# Sheet1.net
KiCad netlist of a schematic drawn in Altium Designer
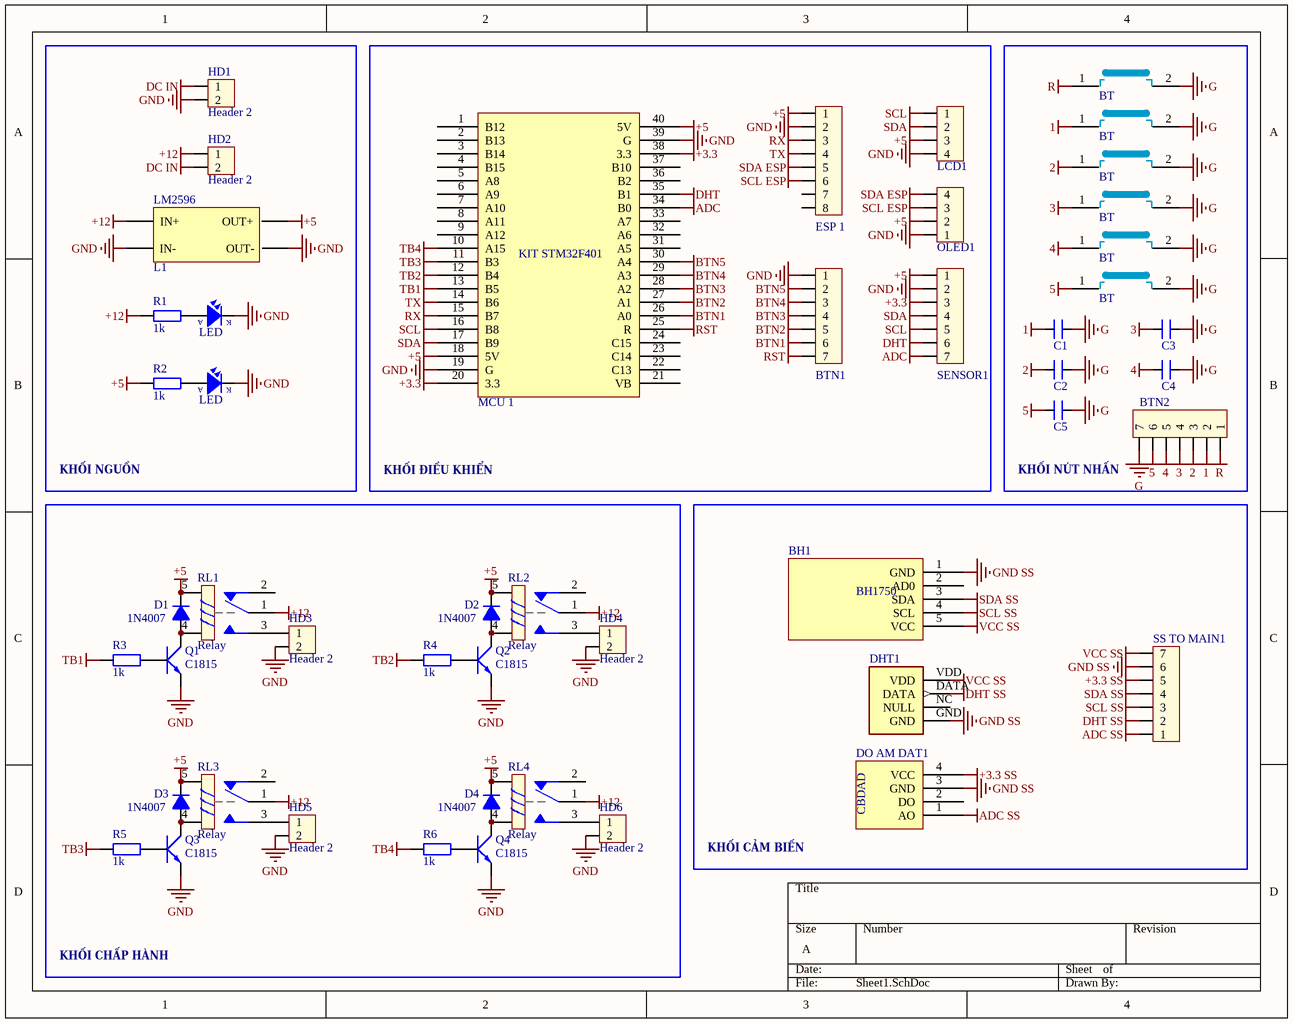
[diagram p0: Sheet1.SchDoc]

(export (version "E")
  (design (tool "Eeschema 10.0.6"))
  (components
    (comp (ref "BH1") (value "BH1750") (footprint "BH1750") (libsource (lib "MY_LIBRARY") (part "BH1750")))
    (comp (ref "BT1") (value "BT") (footprint "SW4") (libsource (lib "MY_LIBRARY") (part "BUTTON")))
    (comp (ref "BT2") (value "BT") (footprint "SW4") (libsource (lib "MY_LIBRARY") (part "BUTTON")))
    (comp (ref "BT3") (value "BT") (footprint "SW4") (libsource (lib "MY_LIBRARY") (part "BUTTON")))
    (comp (ref "BT4") (value "BT") (footprint "SW4") (libsource (lib "MY_LIBRARY") (part "BUTTON")))
    (comp (ref "BT5") (value "BT") (footprint "SW4") (libsource (lib "MY_LIBRARY") (part "BUTTON")))
    (comp (ref "BT6") (value "BT") (footprint "SW4") (libsource (lib "MY_LIBRARY") (part "BUTTON")))
    (comp (ref "BTN1")
      (value "JP7")
      (footprint "CON7")
      (description "Connector 7")
      (libsource (lib "MY_LIBRARY") (part "Con7"))
    )
    (comp (ref "BTN2")
      (value "JP7")
      (footprint "CON7")
      (description "Connector 7")
      (libsource (lib "MY_LIBRARY") (part "Con7"))
    )
    (comp (ref "C1") (value "CAP gom") (footprint "CN1") (libsource (lib "MY_LIBRARY") (part "CAP gom")))
    (comp (ref "C2") (value "CAP gom") (footprint "CN1") (libsource (lib "MY_LIBRARY") (part "CAP gom")))
    (comp (ref "C3") (value "CAP gom") (footprint "CN1") (libsource (lib "MY_LIBRARY") (part "CAP gom")))
    (comp (ref "C4") (value "CAP gom") (footprint "CN1") (libsource (lib "MY_LIBRARY") (part "CAP gom")))
    (comp (ref "C5") (value "CAP gom") (footprint "CN1") (libsource (lib "MY_LIBRARY") (part "CAP gom")))
    (comp (ref "D1")
      (value "1N4007")
      (footprint "D2A")
      (description "Diode 1A")
      (libsource (lib "Thuvien3D") (part "D1A"))
    )
    (comp (ref "D2")
      (value "1N4007")
      (footprint "D2A")
      (description "Diode 1A")
      (libsource (lib "Thuvien3D") (part "D1A"))
    )
    (comp (ref "D3")
      (value "1N4007")
      (footprint "D2A")
      (description "Diode 1A")
      (libsource (lib "Thuvien3D") (part "D1A"))
    )
    (comp (ref "D4")
      (value "1N4007")
      (footprint "D2A")
      (description "Diode 1A")
      (libsource (lib "Thuvien3D") (part "D1A"))
    )
    (comp (ref "DHT1")
      (value "DHT22")
      (footprint "DHT22")
      (description "Capacitive-type humidity and temperature module/sensor")
      (fields (field (name "MF") "Aosong Electronics"))
      (libsource (lib "MY_LIBRARY") (part "DHT22"))
    )
    (comp (ref "DO AM DAT1")
      (value "Cam_bien_do_am_dat")
      (footprint "Am dat")
      (libsource (lib "MY_LIBRARY") (part "Cam_bien_do_am_dat"))
    )
    (comp (ref "ESP 1")
      (value "JP8")
      (footprint "HDR1X8")
      (description "jam 8")
      (libsource (lib "MY_LIBRARY") (part "jam 8"))
    )
    (comp (ref "HD1")
      (value "Header 2")
      (footprint "HED2")
      (description "Header 2 (Green)")
      (libsource (lib "Thuvien3D") (part "Hed2"))
    )
    (comp (ref "HD2")
      (value "Header 2")
      (footprint "HED2")
      (description "Header 2 (Green)")
      (libsource (lib "Thuvien3D") (part "Hed2"))
    )
    (comp (ref "HD3")
      (value "Header 2")
      (footprint "HED2")
      (description "Header 2 (Green)")
      (libsource (lib "Thuvien3D") (part "Hed2"))
    )
    (comp (ref "HD4")
      (value "Header 2")
      (footprint "HED2")
      (description "Header 2 (Green)")
      (libsource (lib "Thuvien3D") (part "Hed2"))
    )
    (comp (ref "HD5")
      (value "Header 2")
      (footprint "HED2")
      (description "Header 2 (Green)")
      (libsource (lib "Thuvien3D") (part "Hed2"))
    )
    (comp (ref "HD6")
      (value "Header 2")
      (footprint "HED2")
      (description "Header 2 (Green)")
      (libsource (lib "Thuvien3D") (part "Hed2"))
    )
    (comp (ref "L1")
      (value "BUCK_LM2596")
      (footprint "BUCK_LM2596")
      (libsource (lib "MY_LIBRARY") (part "BUCK_LM2596"))
    )
    (comp (ref "LCD1")
      (value "JP4")
      (footprint "CON4")
      (description "Connector 4")
      (libsource (lib "MY_LIBRARY") (part "Con4"))
    )
    (comp (ref "LED1")
      (value "LED")
      (footprint "LED-3")
      (description "LED Single colour Green and Red")
      (libsource (lib "MY_LIBRARY") (part "LED"))
    )
    (comp (ref "LED2")
      (value "LED")
      (footprint "LED-3")
      (description "LED Single colour Green and Red")
      (libsource (lib "MY_LIBRARY") (part "LED"))
    )
    (comp (ref "MCU 1")
      (value "KIT STM32F401")
      (footprint "KIT STM32F401")
      (libsource (lib "MY_LIBRARY") (part "KIT STM32F401"))
    )
    (comp (ref "OLED1")
      (value "JP4")
      (footprint "CON4")
      (description "Connector 4")
      (libsource (lib "") (part "Con4_1"))
    )
    (comp (ref "Q1")
      (value "C1815")
      (footprint "QTO-92")
      (description "NPN 600mW, ECB")
      (libsource (lib "Thuvien3D") (part "C1815"))
    )
    (comp (ref "Q2")
      (value "C1815")
      (footprint "QTO-92")
      (description "NPN 600mW, ECB")
      (libsource (lib "Thuvien3D") (part "C1815"))
    )
    (comp (ref "Q3")
      (value "C1815")
      (footprint "QTO-92")
      (description "NPN 600mW, ECB")
      (libsource (lib "Thuvien3D") (part "C1815"))
    )
    (comp (ref "Q4")
      (value "C1815")
      (footprint "QTO-92")
      (description "NPN 600mW, ECB")
      (libsource (lib "Thuvien3D") (part "C1815"))
    )
    (comp (ref "R1")
      (value "1k")
      (footprint "R1/2W")
      (description "Resistor 1/4W")
      (libsource (lib "Thuvien3D") (part "R1/4W"))
    )
    (comp (ref "R2")
      (value "1k")
      (footprint "R1/2W")
      (description "Resistor 1/4W")
      (libsource (lib "Thuvien3D") (part "R1/4W"))
    )
    (comp (ref "R3")
      (value "1k")
      (footprint "R1/2W")
      (description "Resistor 1/4W")
      (libsource (lib "Thuvien3D") (part "R1/4W"))
    )
    (comp (ref "R4")
      (value "1k")
      (footprint "R1/2W")
      (description "Resistor 1/4W")
      (libsource (lib "Thuvien3D") (part "R1/4W"))
    )
    (comp (ref "R5")
      (value "1k")
      (footprint "R1/2W")
      (description "Resistor 1/4W")
      (libsource (lib "Thuvien3D") (part "R1/4W"))
    )
    (comp (ref "R6")
      (value "1k")
      (footprint "R1/2W")
      (description "Resistor 1/4W")
      (libsource (lib "Thuvien3D") (part "R1/4W"))
    )
    (comp (ref "RL1")
      (value "Relay")
      (footprint "RL_SPDT_10A")
      (description "Relay SPDT 5 Pin")
      (libsource (lib "MY_LIBRARY") (part "Relay SRD"))
    )
    (comp (ref "RL2")
      (value "Relay")
      (footprint "RL_SPDT_10A")
      (description "Relay SPDT 5 Pin")
      (libsource (lib "MY_LIBRARY") (part "Relay SRD"))
    )
    (comp (ref "RL3")
      (value "Relay")
      (footprint "RL_SPDT_10A")
      (description "Relay SPDT 5 Pin")
      (libsource (lib "MY_LIBRARY") (part "Relay SRD"))
    )
    (comp (ref "RL4")
      (value "Relay")
      (footprint "RL_SPDT_10A")
      (description "Relay SPDT 5 Pin")
      (libsource (lib "MY_LIBRARY") (part "Relay SRD"))
    )
    (comp (ref "SENSOR1")
      (value "JP7")
      (footprint "CON7")
      (description "Connector 7")
      (libsource (lib "MY_LIBRARY") (part "Con7"))
    )
    (comp (ref "SS TO MAIN1")
      (value "~")
      (footprint "CON7")
      (description "Connector 7")
      (libsource (lib "") (part "Con7_1"))
    )
  )
  (nets
    (net (code "1") (name "+3.3") (class "Default")
      (node (ref "MCU 1") (pin "20") (pinfunction "3.3_20") (pintype "passive"))
      (node (ref "MCU 1") (pin "38") (pinfunction "3.3_38") (pintype "passive"))
      (node (ref "SENSOR1") (pin "3") (pinfunction "3_3") (pintype "passive"))
    )
    (net (code "2") (name "+3.3 SS") (class "Default")
      (node (ref "DO AM DAT1") (pin "4") (pinfunction "VCC_4") (pintype "passive"))
      (node (ref "SS TO MAIN1") (pin "5") (pinfunction "5_5") (pintype "passive"))
    )
    (net (code "3") (name "+5") (class "Default")
      (node (ref "D1") (pin "2") (pinfunction "K_2") (pintype "passive"))
      (node (ref "D2") (pin "2") (pinfunction "K_2") (pintype "passive"))
      (node (ref "D3") (pin "2") (pinfunction "K_2") (pintype "passive"))
      (node (ref "D4") (pin "2") (pinfunction "K_2") (pintype "passive"))
      (node (ref "ESP 1") (pin "1") (pinfunction "1_1") (pintype "passive"))
      (node (ref "L1") (pin "4") (pinfunction "OUT+_4") (pintype "passive"))
      (node (ref "LCD1") (pin "3") (pinfunction "3_3") (pintype "passive"))
      (node (ref "MCU 1") (pin "18") (pinfunction "5V_18") (pintype "passive"))
      (node (ref "MCU 1") (pin "40") (pinfunction "5V_40") (pintype "passive"))
      (node (ref "OLED1") (pin "2") (pinfunction "2_2") (pintype "passive"))
      (node (ref "R2") (pin "2") (pinfunction "2_2") (pintype "passive"))
      (node (ref "RL1") (pin "5") (pinfunction "5_5") (pintype "passive"))
      (node (ref "RL2") (pin "5") (pinfunction "5_5") (pintype "passive"))
      (node (ref "RL3") (pin "5") (pinfunction "5_5") (pintype "passive"))
      (node (ref "RL4") (pin "5") (pinfunction "5_5") (pintype "passive"))
      (node (ref "SENSOR1") (pin "1") (pinfunction "1_1") (pintype "passive"))
    )
    (net (code "4") (name "+12") (class "Default")
      (node (ref "HD2") (pin "1") (pinfunction "1_1") (pintype "passive"))
      (node (ref "L1") (pin "1") (pinfunction "IN+_1") (pintype "passive"))
      (node (ref "R1") (pin "2") (pinfunction "2_2") (pintype "passive"))
      (node (ref "RL1") (pin "1") (pinfunction "1_1") (pintype "passive"))
      (node (ref "RL2") (pin "1") (pinfunction "1_1") (pintype "passive"))
      (node (ref "RL3") (pin "1") (pinfunction "1_1") (pintype "passive"))
      (node (ref "RL4") (pin "1") (pinfunction "1_1") (pintype "passive"))
    )
    (net (code "5") (name "1") (class "Default")
      (node (ref "BT2") (pin "1") (pinfunction "1_1") (pintype "passive"))
      (node (ref "BTN2") (pin "2") (pinfunction "2_2") (pintype "passive"))
      (node (ref "C1") (pin "2") (pinfunction "2_2") (pintype "passive"))
    )
    (net (code "6") (name "2") (class "Default")
      (node (ref "BT3") (pin "1") (pinfunction "1_1") (pintype "passive"))
      (node (ref "BTN2") (pin "3") (pinfunction "3_3") (pintype "passive"))
      (node (ref "C2") (pin "2") (pinfunction "2_2") (pintype "passive"))
    )
    (net (code "7") (name "3") (class "Default")
      (node (ref "BT4") (pin "1") (pinfunction "1_1") (pintype "passive"))
      (node (ref "BTN2") (pin "4") (pinfunction "4_4") (pintype "passive"))
      (node (ref "C3") (pin "2") (pinfunction "2_2") (pintype "passive"))
    )
    (net (code "8") (name "4") (class "Default")
      (node (ref "BT5") (pin "1") (pinfunction "1_1") (pintype "passive"))
      (node (ref "BTN2") (pin "5") (pinfunction "5_5") (pintype "passive"))
      (node (ref "C4") (pin "2") (pinfunction "2_2") (pintype "passive"))
    )
    (net (code "9") (name "5") (class "Default")
      (node (ref "BT6") (pin "1") (pinfunction "1_1") (pintype "passive"))
      (node (ref "BTN2") (pin "6") (pinfunction "6_6") (pintype "passive"))
      (node (ref "C5") (pin "2") (pinfunction "2_2") (pintype "passive"))
    )
    (net (code "10") (name "ADC") (class "Default")
      (node (ref "MCU 1") (pin "34") (pinfunction "B0_34") (pintype "passive"))
      (node (ref "SENSOR1") (pin "7") (pinfunction "7_7") (pintype "passive"))
    )
    (net (code "11") (name "ADC SS") (class "Default")
      (node (ref "DO AM DAT1") (pin "1") (pinfunction "AO_1") (pintype "passive"))
      (node (ref "SS TO MAIN1") (pin "1") (pinfunction "1_1") (pintype "passive"))
    )
    (net (code "12") (name "BTN1") (class "Default")
      (node (ref "BTN1") (pin "6") (pinfunction "6_6") (pintype "passive"))
      (node (ref "MCU 1") (pin "26") (pinfunction "A0_26") (pintype "passive"))
    )
    (net (code "13") (name "BTN2") (class "Default")
      (node (ref "BTN1") (pin "5") (pinfunction "5_5") (pintype "passive"))
      (node (ref "MCU 1") (pin "27") (pinfunction "A1_27") (pintype "passive"))
    )
    (net (code "14") (name "BTN3") (class "Default")
      (node (ref "BTN1") (pin "4") (pinfunction "4_4") (pintype "passive"))
      (node (ref "MCU 1") (pin "28") (pinfunction "A2_28") (pintype "passive"))
    )
    (net (code "15") (name "BTN4") (class "Default")
      (node (ref "BTN1") (pin "3") (pinfunction "3_3") (pintype "passive"))
      (node (ref "MCU 1") (pin "29") (pinfunction "A3_29") (pintype "passive"))
    )
    (net (code "16") (name "BTN5") (class "Default")
      (node (ref "BTN1") (pin "2") (pinfunction "2_2") (pintype "passive"))
      (node (ref "MCU 1") (pin "30") (pinfunction "A4_30") (pintype "passive"))
    )
    (net (code "17") (name "DC IN") (class "Default")
      (node (ref "HD1") (pin "1") (pinfunction "1_1") (pintype "passive"))
      (node (ref "HD2") (pin "2") (pinfunction "2_2") (pintype "passive"))
    )
    (net (code "18") (name "DHT") (class "Default")
      (node (ref "MCU 1") (pin "35") (pinfunction "B1_35") (pintype "passive"))
      (node (ref "SENSOR1") (pin "6") (pinfunction "6_6") (pintype "passive"))
    )
    (net (code "19") (name "DHT SS") (class "Default")
      (node (ref "DHT1") (pin "DATA") (pinfunction "DATA_DATA") (pintype "output"))
      (node (ref "SS TO MAIN1") (pin "2") (pinfunction "2_2") (pintype "passive"))
    )
    (net (code "20") (name "G") (class "Default")
      (node (ref "BT1") (pin "2") (pinfunction "2_2") (pintype "passive"))
      (node (ref "BT2") (pin "2") (pinfunction "2_2") (pintype "passive"))
      (node (ref "BT3") (pin "2") (pinfunction "2_2") (pintype "passive"))
      (node (ref "BT4") (pin "2") (pinfunction "2_2") (pintype "passive"))
      (node (ref "BT5") (pin "2") (pinfunction "2_2") (pintype "passive"))
      (node (ref "BT6") (pin "2") (pinfunction "2_2") (pintype "passive"))
      (node (ref "BTN2") (pin "7") (pinfunction "7_7") (pintype "passive"))
      (node (ref "C1") (pin "1") (pinfunction "1_1") (pintype "passive"))
      (node (ref "C2") (pin "1") (pinfunction "1_1") (pintype "passive"))
      (node (ref "C3") (pin "1") (pinfunction "1_1") (pintype "passive"))
      (node (ref "C4") (pin "1") (pinfunction "1_1") (pintype "passive"))
      (node (ref "C5") (pin "1") (pinfunction "1_1") (pintype "passive"))
    )
    (net (code "21") (name "GND") (class "Default")
      (node (ref "BTN1") (pin "1") (pinfunction "1_1") (pintype "passive"))
      (node (ref "ESP 1") (pin "2") (pinfunction "2_2") (pintype "passive"))
      (node (ref "HD1") (pin "2") (pinfunction "2_2") (pintype "passive"))
      (node (ref "HD3") (pin "2") (pinfunction "2_2") (pintype "passive"))
      (node (ref "HD4") (pin "2") (pinfunction "2_2") (pintype "passive"))
      (node (ref "HD5") (pin "2") (pinfunction "2_2") (pintype "passive"))
      (node (ref "HD6") (pin "2") (pinfunction "2_2") (pintype "passive"))
      (node (ref "L1") (pin "2") (pinfunction "IN-_2") (pintype "passive"))
      (node (ref "L1") (pin "3") (pinfunction "OUT-_3") (pintype "passive"))
      (node (ref "LCD1") (pin "4") (pinfunction "4_4") (pintype "passive"))
      (node (ref "LED1") (pin "2") (pinfunction "K_2") (pintype "passive"))
      (node (ref "LED2") (pin "2") (pinfunction "K_2") (pintype "passive"))
      (node (ref "MCU 1") (pin "19") (pinfunction "G_19") (pintype "passive"))
      (node (ref "MCU 1") (pin "39") (pinfunction "G_39") (pintype "passive"))
      (node (ref "OLED1") (pin "1") (pinfunction "1_1") (pintype "passive"))
      (node (ref "Q1") (pin "1") (pinfunction "E_1") (pintype "passive"))
      (node (ref "Q2") (pin "1") (pinfunction "E_1") (pintype "passive"))
      (node (ref "Q3") (pin "1") (pinfunction "E_1") (pintype "passive"))
      (node (ref "Q4") (pin "1") (pinfunction "E_1") (pintype "passive"))
      (node (ref "SENSOR1") (pin "2") (pinfunction "2_2") (pintype "passive"))
    )
    (net (code "22") (name "GND SS") (class "Default")
      (node (ref "BH1") (pin "1") (pinfunction "GND_1") (pintype "passive"))
      (node (ref "DHT1") (pin "GND") (pinfunction "GND_GND") (pintype "power_in"))
      (node (ref "DO AM DAT1") (pin "3") (pinfunction "GND_3") (pintype "passive"))
      (node (ref "SS TO MAIN1") (pin "6") (pinfunction "6_6") (pintype "passive"))
    )
    (net (code "23") (name "Net-(D1-A)") (class "Default")
      (node (ref "D1") (pin "1") (pinfunction "A_1") (pintype "passive"))
      (node (ref "Q1") (pin "2") (pinfunction "C_2") (pintype "passive"))
      (node (ref "RL1") (pin "4") (pinfunction "4_4") (pintype "passive"))
    )
    (net (code "24") (name "Net-(D2-A)") (class "Default")
      (node (ref "D2") (pin "1") (pinfunction "A_1") (pintype "passive"))
      (node (ref "Q2") (pin "2") (pinfunction "C_2") (pintype "passive"))
      (node (ref "RL2") (pin "4") (pinfunction "4_4") (pintype "passive"))
    )
    (net (code "25") (name "Net-(D3-A)") (class "Default")
      (node (ref "D3") (pin "1") (pinfunction "A_1") (pintype "passive"))
      (node (ref "Q3") (pin "2") (pinfunction "C_2") (pintype "passive"))
      (node (ref "RL3") (pin "4") (pinfunction "4_4") (pintype "passive"))
    )
    (net (code "26") (name "Net-(D4-A)") (class "Default")
      (node (ref "D4") (pin "1") (pinfunction "A_1") (pintype "passive"))
      (node (ref "Q4") (pin "2") (pinfunction "C_2") (pintype "passive"))
      (node (ref "RL4") (pin "4") (pinfunction "4_4") (pintype "passive"))
    )
    (net (code "27") (name "Net-(HD3-Pad1)") (class "Default")
      (node (ref "HD3") (pin "1") (pinfunction "1_1") (pintype "passive"))
      (node (ref "RL1") (pin "3") (pinfunction "3_3") (pintype "passive"))
    )
    (net (code "28") (name "Net-(HD4-Pad1)") (class "Default")
      (node (ref "HD4") (pin "1") (pinfunction "1_1") (pintype "passive"))
      (node (ref "RL2") (pin "3") (pinfunction "3_3") (pintype "passive"))
    )
    (net (code "29") (name "Net-(HD5-Pad1)") (class "Default")
      (node (ref "HD5") (pin "1") (pinfunction "1_1") (pintype "passive"))
      (node (ref "RL3") (pin "3") (pinfunction "3_3") (pintype "passive"))
    )
    (net (code "30") (name "Net-(HD6-Pad1)") (class "Default")
      (node (ref "HD6") (pin "1") (pinfunction "1_1") (pintype "passive"))
      (node (ref "RL4") (pin "3") (pinfunction "3_3") (pintype "passive"))
    )
    (net (code "31") (name "Net-(LED1-A)") (class "Default")
      (node (ref "LED1") (pin "1") (pinfunction "A_1") (pintype "passive"))
      (node (ref "R1") (pin "1") (pinfunction "1_1") (pintype "passive"))
    )
    (net (code "32") (name "Net-(LED2-A)") (class "Default")
      (node (ref "LED2") (pin "1") (pinfunction "A_1") (pintype "passive"))
      (node (ref "R2") (pin "1") (pinfunction "1_1") (pintype "passive"))
    )
    (net (code "33") (name "Net-(Q1-B)") (class "Default")
      (node (ref "Q1") (pin "3") (pinfunction "B_3") (pintype "passive"))
      (node (ref "R3") (pin "1") (pinfunction "1_1") (pintype "passive"))
    )
    (net (code "34") (name "Net-(Q2-B)") (class "Default")
      (node (ref "Q2") (pin "3") (pinfunction "B_3") (pintype "passive"))
      (node (ref "R4") (pin "1") (pinfunction "1_1") (pintype "passive"))
    )
    (net (code "35") (name "Net-(Q3-B)") (class "Default")
      (node (ref "Q3") (pin "3") (pinfunction "B_3") (pintype "passive"))
      (node (ref "R5") (pin "1") (pinfunction "1_1") (pintype "passive"))
    )
    (net (code "36") (name "Net-(Q4-B)") (class "Default")
      (node (ref "Q4") (pin "3") (pinfunction "B_3") (pintype "passive"))
      (node (ref "R6") (pin "1") (pinfunction "1_1") (pintype "passive"))
    )
    (net (code "37") (name "R") (class "Default")
      (node (ref "BT1") (pin "1") (pinfunction "1_1") (pintype "passive"))
      (node (ref "BTN2") (pin "1") (pinfunction "1_1") (pintype "passive"))
    )
    (net (code "38") (name "RST") (class "Default")
      (node (ref "BTN1") (pin "7") (pinfunction "7_7") (pintype "passive"))
      (node (ref "MCU 1") (pin "25") (pinfunction "R_25") (pintype "passive"))
    )
    (net (code "39") (name "RX") (class "Default")
      (node (ref "ESP 1") (pin "3") (pinfunction "3_3") (pintype "passive"))
      (node (ref "MCU 1") (pin "15") (pinfunction "B7_15") (pintype "passive"))
    )
    (net (code "40") (name "SCL") (class "Default")
      (node (ref "LCD1") (pin "1") (pinfunction "1_1") (pintype "passive"))
      (node (ref "MCU 1") (pin "16") (pinfunction "B8_16") (pintype "passive"))
      (node (ref "SENSOR1") (pin "5") (pinfunction "5_5") (pintype "passive"))
    )
    (net (code "41") (name "SCL ESP") (class "Default")
      (node (ref "ESP 1") (pin "6") (pinfunction "6_6") (pintype "passive"))
      (node (ref "OLED1") (pin "3") (pinfunction "3_3") (pintype "passive"))
    )
    (net (code "42") (name "SCL SS") (class "Default")
      (node (ref "BH1") (pin "4") (pinfunction "SCL_4") (pintype "passive"))
      (node (ref "SS TO MAIN1") (pin "3") (pinfunction "3_3") (pintype "passive"))
    )
    (net (code "43") (name "SDA") (class "Default")
      (node (ref "LCD1") (pin "2") (pinfunction "2_2") (pintype "passive"))
      (node (ref "MCU 1") (pin "17") (pinfunction "B9_17") (pintype "passive"))
      (node (ref "SENSOR1") (pin "4") (pinfunction "4_4") (pintype "passive"))
    )
    (net (code "44") (name "SDA ESP") (class "Default")
      (node (ref "ESP 1") (pin "5") (pinfunction "5_5") (pintype "passive"))
      (node (ref "OLED1") (pin "4") (pinfunction "4_4") (pintype "passive"))
    )
    (net (code "45") (name "SDA SS") (class "Default")
      (node (ref "BH1") (pin "3") (pinfunction "SDA_3") (pintype "passive"))
      (node (ref "SS TO MAIN1") (pin "4") (pinfunction "4_4") (pintype "passive"))
    )
    (net (code "46") (name "TB1") (class "Default")
      (node (ref "MCU 1") (pin "13") (pinfunction "B5_13") (pintype "passive"))
      (node (ref "R3") (pin "2") (pinfunction "2_2") (pintype "passive"))
    )
    (net (code "47") (name "TB2") (class "Default")
      (node (ref "MCU 1") (pin "12") (pinfunction "B4_12") (pintype "passive"))
      (node (ref "R4") (pin "2") (pinfunction "2_2") (pintype "passive"))
    )
    (net (code "48") (name "TB3") (class "Default")
      (node (ref "MCU 1") (pin "11") (pinfunction "B3_11") (pintype "passive"))
      (node (ref "R5") (pin "2") (pinfunction "2_2") (pintype "passive"))
    )
    (net (code "49") (name "TB4") (class "Default")
      (node (ref "MCU 1") (pin "10") (pinfunction "A15_10") (pintype "passive"))
      (node (ref "R6") (pin "2") (pinfunction "2_2") (pintype "passive"))
    )
    (net (code "50") (name "TX") (class "Default")
      (node (ref "ESP 1") (pin "4") (pinfunction "4_4") (pintype "passive"))
      (node (ref "MCU 1") (pin "14") (pinfunction "B6_14") (pintype "passive"))
    )
    (net (code "51") (name "VCC SS") (class "Default")
      (node (ref "BH1") (pin "5") (pinfunction "VCC_5") (pintype "passive"))
      (node (ref "DHT1") (pin "VDD") (pinfunction "VDD_VDD") (pintype "power_in"))
      (node (ref "SS TO MAIN1") (pin "7") (pinfunction "7_7") (pintype "passive"))
    )
    (net (code "52") (name "unconnected-(BH1-AD0-Pad2)") (class "Default")
      (node (ref "BH1") (pin "2") (pinfunction "AD0_2") (pintype "passive"))
    )
    (net (code "53") (name "unconnected-(DHT1-NULL-PadNC)") (class "Default")
      (node (ref "DHT1") (pin "NC") (pinfunction "NULL_NC") (pintype "passive"))
    )
    (net (code "54") (name "unconnected-(DO AM DAT1-DO-Pad2)") (class "Default")
      (node (ref "DO AM DAT1") (pin "2") (pinfunction "DO_2") (pintype "passive"))
    )
    (net (code "55") (name "unconnected-(ESP 1-Pad7)") (class "Default")
      (node (ref "ESP 1") (pin "7") (pinfunction "7_7") (pintype "passive"))
    )
    (net (code "56") (name "unconnected-(ESP 1-Pad8)") (class "Default")
      (node (ref "ESP 1") (pin "8") (pinfunction "8_8") (pintype "passive"))
    )
    (net (code "57") (name "unconnected-(MCU 1-A5-Pad31)") (class "Default")
      (node (ref "MCU 1") (pin "31") (pinfunction "A5_31") (pintype "passive"))
    )
    (net (code "58") (name "unconnected-(MCU 1-A6-Pad32)") (class "Default")
      (node (ref "MCU 1") (pin "32") (pinfunction "A6_32") (pintype "passive"))
    )
    (net (code "59") (name "unconnected-(MCU 1-A7-Pad33)") (class "Default")
      (node (ref "MCU 1") (pin "33") (pinfunction "A7_33") (pintype "passive"))
    )
    (net (code "60") (name "unconnected-(MCU 1-A8-Pad5)") (class "Default")
      (node (ref "MCU 1") (pin "5") (pinfunction "A8_5") (pintype "passive"))
    )
    (net (code "61") (name "unconnected-(MCU 1-A9-Pad6)") (class "Default")
      (node (ref "MCU 1") (pin "6") (pinfunction "A9_6") (pintype "passive"))
    )
    (net (code "62") (name "unconnected-(MCU 1-A10-Pad7)") (class "Default")
      (node (ref "MCU 1") (pin "7") (pinfunction "A10_7") (pintype "passive"))
    )
    (net (code "63") (name "unconnected-(MCU 1-A11-Pad8)") (class "Default")
      (node (ref "MCU 1") (pin "8") (pinfunction "A11_8") (pintype "passive"))
    )
    (net (code "64") (name "unconnected-(MCU 1-A12-Pad9)") (class "Default")
      (node (ref "MCU 1") (pin "9") (pinfunction "A12_9") (pintype "passive"))
    )
    (net (code "65") (name "unconnected-(MCU 1-B2-Pad36)") (class "Default")
      (node (ref "MCU 1") (pin "36") (pinfunction "B2_36") (pintype "passive"))
    )
    (net (code "66") (name "unconnected-(MCU 1-B10-Pad37)") (class "Default")
      (node (ref "MCU 1") (pin "37") (pinfunction "B10_37") (pintype "passive"))
    )
    (net (code "67") (name "unconnected-(MCU 1-B12-Pad1)") (class "Default")
      (node (ref "MCU 1") (pin "1") (pinfunction "B12_1") (pintype "passive"))
    )
    (net (code "68") (name "unconnected-(MCU 1-B13-Pad2)") (class "Default")
      (node (ref "MCU 1") (pin "2") (pinfunction "B13_2") (pintype "passive"))
    )
    (net (code "69") (name "unconnected-(MCU 1-B14-Pad3)") (class "Default")
      (node (ref "MCU 1") (pin "3") (pinfunction "B14_3") (pintype "passive"))
    )
    (net (code "70") (name "unconnected-(MCU 1-B15-Pad4)") (class "Default")
      (node (ref "MCU 1") (pin "4") (pinfunction "B15_4") (pintype "passive"))
    )
    (net (code "71") (name "unconnected-(MCU 1-C13-Pad22)") (class "Default")
      (node (ref "MCU 1") (pin "22") (pinfunction "C13_22") (pintype "passive"))
    )
    (net (code "72") (name "unconnected-(MCU 1-C14-Pad23)") (class "Default")
      (node (ref "MCU 1") (pin "23") (pinfunction "C14_23") (pintype "passive"))
    )
    (net (code "73") (name "unconnected-(MCU 1-C15-Pad24)") (class "Default")
      (node (ref "MCU 1") (pin "24") (pinfunction "C15_24") (pintype "passive"))
    )
    (net (code "74") (name "unconnected-(MCU 1-VB-Pad21)") (class "Default")
      (node (ref "MCU 1") (pin "21") (pinfunction "VB_21") (pintype "passive"))
    )
    (net (code "75") (name "unconnected-(RL1-Pad2)") (class "Default")
      (node (ref "RL1") (pin "2") (pinfunction "2_2") (pintype "passive"))
    )
    (net (code "76") (name "unconnected-(RL2-Pad2)") (class "Default")
      (node (ref "RL2") (pin "2") (pinfunction "2_2") (pintype "passive"))
    )
    (net (code "77") (name "unconnected-(RL3-Pad2)") (class "Default")
      (node (ref "RL3") (pin "2") (pinfunction "2_2") (pintype "passive"))
    )
    (net (code "78") (name "unconnected-(RL4-Pad2)") (class "Default")
      (node (ref "RL4") (pin "2") (pinfunction "2_2") (pintype "passive"))
    )
  )
)
